# MacroStepper_v2_0.net
KiCad netlist of a schematic drawn in EAGLE
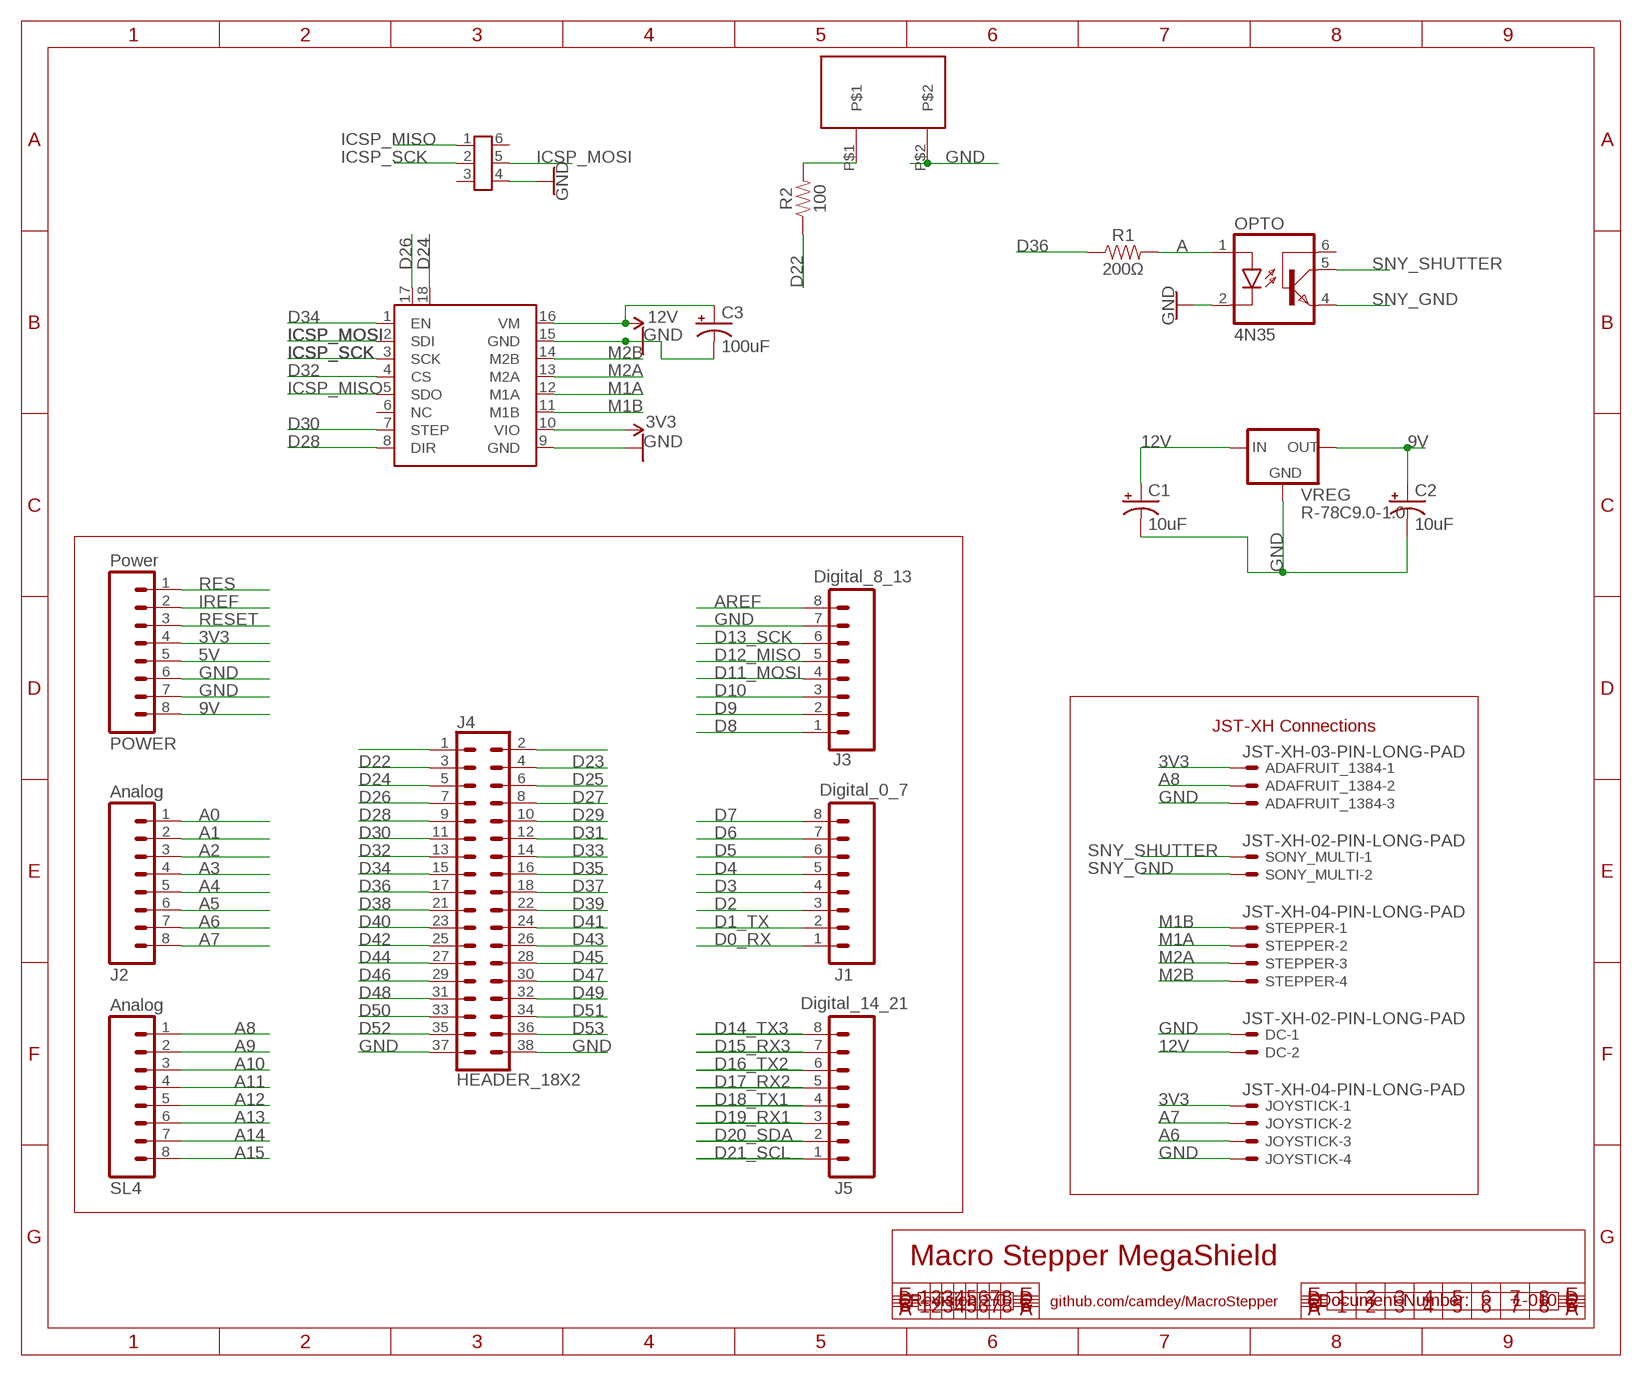
[diagram p0: schematic, sheet 1]

(export (version "E")
  (design (tool "Eeschema 10.0.6"))
  (components
    (comp (ref "ADAFRUIT_1384")
      (value "JST-XH-03-PIN-LONG-PAD")
      (footprint "eagle-import:JST-XH-03-PACKAGE-LONG-PAD")
      (libsource (lib "eagle-import") (part "JST-XH-03-PIN-LONG-PAD"))
    )
    (comp (ref "C1")
      (value "10uF")
      (footprint "eagle-import:CPOL-RADIAL-2.5MM-5MM")
      (libsource (lib "eagle-import") (part "10UF-POLAR-RADIAL-2.5MM-25V-20%"))
    )
    (comp (ref "C2")
      (value "10uF")
      (footprint "eagle-import:CPOL-RADIAL-2.5MM-5MM")
      (libsource (lib "eagle-import") (part "10UF-POLAR-RADIAL-2.5MM-25V-20%"))
    )
    (comp (ref "C3")
      (value "100uF")
      (footprint "eagle-import:CPOL-RADIAL-2.5MM-6.5MM")
      (libsource (lib "eagle-import") (part "100UF-POLAR-RADIAL-2.5MM-25V-20%"))
    )
    (comp (ref "DC")
      (value "JST-XH-02-PIN-LONG-PAD")
      (footprint "eagle-import:JST-XH-02-PACKAGE-LONG-PAD")
      (libsource (lib "eagle-import") (part "JST-XH-02-PIN-LONG-PAD"))
    )
    (comp (ref "ICSP")
      (value "MEGA_ICSP")
      (footprint "eagle-import:MEGA_ICSP")
      (libsource (lib "eagle-import") (part "MEGA_ICSP"))
    )
    (comp (ref "J1")
      (value "Digital_0_7")
      (footprint "eagle-import:1X08")
      (libsource (lib "eagle-import") (part "M08"))
    )
    (comp (ref "J2")
      (value "Analog")
      (footprint "eagle-import:1X08")
      (libsource (lib "eagle-import") (part "M08"))
    )
    (comp (ref "J3")
      (value "Digital_8_13")
      (footprint "eagle-import:1X08")
      (libsource (lib "eagle-import") (part "M08"))
    )
    (comp (ref "J4")
      (value "HEADER_18X2")
      (footprint "eagle-import:2X18")
      (libsource (lib "eagle-import") (part "HEADER_18X2"))
    )
    (comp (ref "J5")
      (value "Digital_14_21")
      (footprint "eagle-import:1X08")
      (libsource (lib "eagle-import") (part "M08"))
    )
    (comp (ref "JOYSTICK")
      (value "JST-XH-04-PIN-LONG-PAD")
      (footprint "eagle-import:JST-XH-04-PACKAGE-LONG-PAD")
      (libsource (lib "eagle-import") (part "JST-XH-04-PIN-LONG-PAD"))
    )
    (comp (ref "OPTO")
      (value "4N35")
      (footprint "eagle-import:DIL06")
      (fields (field (name "MF") "FAIRCHILD SEMICONDUCTOR"))
      (libsource (lib "eagle-import") (part "4N35"))
    )
    (comp (ref "PIEZO")
      (value "PS1240P02BT")
      (footprint "eagle-import:PS1240P02BT")
      (fields (field (name "MF") "TDK"))
      (libsource (lib "eagle-import") (part "PS1240P02BT"))
    )
    (comp (ref "POWER")
      (value "Power")
      (footprint "eagle-import:1X08")
      (libsource (lib "eagle-import") (part "M08"))
    )
    (comp (ref "R1")
      (value "200Ω")
      (footprint "eagle-import:AXIAL-0.3")
      (libsource (lib "eagle-import") (part "RESISTORAXIAL-0.3"))
    )
    (comp (ref "R2")
      (value "100")
      (footprint "eagle-import:AXIAL-0.3")
      (libsource (lib "eagle-import") (part "100OHM-HORIZ-1/4W-1%"))
    )
    (comp (ref "SL4")
      (value "Analog")
      (footprint "eagle-import:1X08")
      (libsource (lib "eagle-import") (part "M08"))
    )
    (comp (ref "SONY_MULTI")
      (value "JST-XH-02-PIN-LONG-PAD")
      (footprint "eagle-import:JST-XH-02-PACKAGE-LONG-PAD")
      (libsource (lib "eagle-import") (part "JST-XH-02-PIN-LONG-PAD"))
    )
    (comp (ref "STEPPER")
      (value "JST-XH-04-PIN-LONG-PAD")
      (footprint "eagle-import:JST-XH-04-PACKAGE-LONG-PAD")
      (libsource (lib "eagle-import") (part "JST-XH-04-PIN-LONG-PAD"))
    )
    (comp (ref "TMC2130")
      (value "TMC2130")
      (footprint "eagle-import:DIL16")
      (libsource (lib "eagle-import") (part "TMC2130"))
    )
    (comp (ref "VREG")
      (value "R-78C9.0-1.0")
      (footprint "eagle-import:SIP3")
      (fields (field (name "MF") "Recom"))
      (libsource (lib "eagle-import") (part "R-78C-1.09.0"))
    )
  )
  (nets
    (net (code "1") (name "/5V") (class "Default")
      (node (ref "POWER") (pin "5") (pinfunction "5_5") (pintype "passive"))
    )
    (net (code "2") (name "/9V") (class "Default")
      (node (ref "C2") (pin "1") (pinfunction "+_1") (pintype "passive"))
      (node (ref "POWER") (pin "8") (pinfunction "8_8") (pintype "passive"))
      (node (ref "VREG") (pin "3") (pinfunction "OUT_3") (pintype "passive"))
    )
    (net (code "3") (name "/A") (class "Default")
      (node (ref "OPTO") (pin "1") (pinfunction "A_1") (pintype "passive"))
      (node (ref "R1") (pin "P$2") (pinfunction "2_P$2") (pintype "passive"))
    )
    (net (code "4") (name "/A0") (class "Default")
      (node (ref "J2") (pin "1") (pinfunction "1_1") (pintype "passive"))
    )
    (net (code "5") (name "/A1") (class "Default")
      (node (ref "J2") (pin "2") (pinfunction "2_2") (pintype "passive"))
    )
    (net (code "6") (name "/A2") (class "Default")
      (node (ref "J2") (pin "3") (pinfunction "3_3") (pintype "passive"))
    )
    (net (code "7") (name "/A3") (class "Default")
      (node (ref "J2") (pin "4") (pinfunction "4_4") (pintype "passive"))
    )
    (net (code "8") (name "/A4") (class "Default")
      (node (ref "J2") (pin "5") (pinfunction "5_5") (pintype "passive"))
    )
    (net (code "9") (name "/A5") (class "Default")
      (node (ref "J2") (pin "6") (pinfunction "6_6") (pintype "passive"))
    )
    (net (code "10") (name "/A6") (class "Default")
      (node (ref "J2") (pin "7") (pinfunction "7_7") (pintype "passive"))
      (node (ref "JOYSTICK") (pin "3") (pinfunction "S_3") (pintype "passive"))
    )
    (net (code "11") (name "/A7") (class "Default")
      (node (ref "J2") (pin "8") (pinfunction "8_8") (pintype "passive"))
      (node (ref "JOYSTICK") (pin "2") (pinfunction "S_2") (pintype "passive"))
    )
    (net (code "12") (name "/A8") (class "Default")
      (node (ref "ADAFRUIT_1384") (pin "2") (pinfunction "S_2") (pintype "passive"))
      (node (ref "SL4") (pin "1") (pinfunction "1_1") (pintype "passive"))
    )
    (net (code "13") (name "/A9") (class "Default")
      (node (ref "SL4") (pin "2") (pinfunction "2_2") (pintype "passive"))
    )
    (net (code "14") (name "/A10") (class "Default")
      (node (ref "SL4") (pin "3") (pinfunction "3_3") (pintype "passive"))
    )
    (net (code "15") (name "/A11") (class "Default")
      (node (ref "SL4") (pin "4") (pinfunction "4_4") (pintype "passive"))
    )
    (net (code "16") (name "/A12") (class "Default")
      (node (ref "SL4") (pin "5") (pinfunction "5_5") (pintype "passive"))
    )
    (net (code "17") (name "/A13") (class "Default")
      (node (ref "SL4") (pin "6") (pinfunction "6_6") (pintype "passive"))
    )
    (net (code "18") (name "/A14") (class "Default")
      (node (ref "SL4") (pin "7") (pinfunction "7_7") (pintype "passive"))
    )
    (net (code "19") (name "/A15") (class "Default")
      (node (ref "SL4") (pin "8") (pinfunction "8_8") (pintype "passive"))
    )
    (net (code "20") (name "/AREF") (class "Default")
      (node (ref "J3") (pin "8") (pinfunction "8_8") (pintype "passive"))
    )
    (net (code "21") (name "/D0_RX") (class "Default")
      (node (ref "J1") (pin "1") (pinfunction "1_1") (pintype "passive"))
    )
    (net (code "22") (name "/D1_TX") (class "Default")
      (node (ref "J1") (pin "2") (pinfunction "2_2") (pintype "passive"))
    )
    (net (code "23") (name "/D2") (class "Default")
      (node (ref "J1") (pin "3") (pinfunction "3_3") (pintype "passive"))
    )
    (net (code "24") (name "/D3") (class "Default")
      (node (ref "J1") (pin "4") (pinfunction "4_4") (pintype "passive"))
    )
    (net (code "25") (name "/D4") (class "Default")
      (node (ref "J1") (pin "5") (pinfunction "5_5") (pintype "passive"))
    )
    (net (code "26") (name "/D5") (class "Default")
      (node (ref "J1") (pin "6") (pinfunction "6_6") (pintype "passive"))
    )
    (net (code "27") (name "/D6") (class "Default")
      (node (ref "J1") (pin "7") (pinfunction "7_7") (pintype "passive"))
    )
    (net (code "28") (name "/D7") (class "Default")
      (node (ref "J1") (pin "8") (pinfunction "8_8") (pintype "passive"))
    )
    (net (code "29") (name "/D8") (class "Default")
      (node (ref "J3") (pin "1") (pinfunction "1_1") (pintype "passive"))
    )
    (net (code "30") (name "/D9") (class "Default")
      (node (ref "J3") (pin "2") (pinfunction "2_2") (pintype "passive"))
    )
    (net (code "31") (name "/D10") (class "Default")
      (node (ref "J3") (pin "3") (pinfunction "3_3") (pintype "passive"))
    )
    (net (code "32") (name "/D11_MOSI") (class "Default")
      (node (ref "J3") (pin "4") (pinfunction "4_4") (pintype "passive"))
    )
    (net (code "33") (name "/D12_MISO") (class "Default")
      (node (ref "J3") (pin "5") (pinfunction "5_5") (pintype "passive"))
    )
    (net (code "34") (name "/D13_SCK") (class "Default")
      (node (ref "J3") (pin "6") (pinfunction "6_6") (pintype "passive"))
    )
    (net (code "35") (name "/D14_TX3") (class "Default")
      (node (ref "J5") (pin "8") (pinfunction "8_8") (pintype "passive"))
    )
    (net (code "36") (name "/D15_RX3") (class "Default")
      (node (ref "J5") (pin "7") (pinfunction "7_7") (pintype "passive"))
    )
    (net (code "37") (name "/D16_TX2") (class "Default")
      (node (ref "J5") (pin "6") (pinfunction "6_6") (pintype "passive"))
    )
    (net (code "38") (name "/D17_RX2") (class "Default")
      (node (ref "J5") (pin "5") (pinfunction "5_5") (pintype "passive"))
    )
    (net (code "39") (name "/D18_TX1") (class "Default")
      (node (ref "J5") (pin "4") (pinfunction "4_4") (pintype "passive"))
    )
    (net (code "40") (name "/D19_RX1") (class "Default")
      (node (ref "J5") (pin "3") (pinfunction "3_3") (pintype "passive"))
    )
    (net (code "41") (name "/D20_SDA") (class "Default")
      (node (ref "J5") (pin "2") (pinfunction "2_2") (pintype "passive"))
    )
    (net (code "42") (name "/D21_SCL") (class "Default")
      (node (ref "J5") (pin "1") (pinfunction "1_1") (pintype "passive"))
    )
    (net (code "43") (name "/D22") (class "Default")
      (node (ref "J4") (pin "3") (pinfunction "D22_3") (pintype "bidirectional"))
      (node (ref "R2") (pin "P$1") (pinfunction "1_P$1") (pintype "passive"))
    )
    (net (code "44") (name "/D23") (class "Default")
      (node (ref "J4") (pin "4") (pinfunction "D23_4") (pintype "bidirectional"))
    )
    (net (code "45") (name "/D24") (class "Default")
      (node (ref "J4") (pin "5") (pinfunction "D24_5") (pintype "bidirectional"))
      (node (ref "TMC2130") (pin "18") (pinfunction "DIAG1_18") (pintype "output"))
    )
    (net (code "46") (name "/D25") (class "Default")
      (node (ref "J4") (pin "6") (pinfunction "D25_6") (pintype "bidirectional"))
    )
    (net (code "47") (name "/D26") (class "Default")
      (node (ref "J4") (pin "7") (pinfunction "D26_7") (pintype "bidirectional"))
      (node (ref "TMC2130") (pin "17") (pinfunction "DIAG0_17") (pintype "output"))
    )
    (net (code "48") (name "/D27") (class "Default")
      (node (ref "J4") (pin "8") (pinfunction "D27_8") (pintype "bidirectional"))
    )
    (net (code "49") (name "/D28") (class "Default")
      (node (ref "J4") (pin "9") (pinfunction "D28_9") (pintype "bidirectional"))
      (node (ref "TMC2130") (pin "8") (pinfunction "DIR_8") (pintype "input"))
    )
    (net (code "50") (name "/D29") (class "Default")
      (node (ref "J4") (pin "10") (pinfunction "D29_10") (pintype "bidirectional"))
    )
    (net (code "51") (name "/D30") (class "Default")
      (node (ref "J4") (pin "11") (pinfunction "D30_11") (pintype "bidirectional"))
      (node (ref "TMC2130") (pin "7") (pinfunction "STEP_7") (pintype "input"))
    )
    (net (code "52") (name "/D31") (class "Default")
      (node (ref "J4") (pin "12") (pinfunction "D31_12") (pintype "bidirectional"))
    )
    (net (code "53") (name "/D32") (class "Default")
      (node (ref "J4") (pin "13") (pinfunction "D32_13") (pintype "bidirectional"))
      (node (ref "TMC2130") (pin "4") (pinfunction "CS_4") (pintype "input"))
    )
    (net (code "54") (name "/D33") (class "Default")
      (node (ref "J4") (pin "14") (pinfunction "D33_14") (pintype "bidirectional"))
    )
    (net (code "55") (name "/D34") (class "Default")
      (node (ref "J4") (pin "15") (pinfunction "D34_15") (pintype "bidirectional"))
      (node (ref "TMC2130") (pin "1") (pinfunction "EN_1") (pintype "input"))
    )
    (net (code "56") (name "/D35") (class "Default")
      (node (ref "J4") (pin "16") (pinfunction "D35_16") (pintype "bidirectional"))
    )
    (net (code "57") (name "/D36") (class "Default")
      (node (ref "J4") (pin "17") (pinfunction "D36_17") (pintype "bidirectional"))
      (node (ref "R1") (pin "P$1") (pinfunction "1_P$1") (pintype "passive"))
    )
    (net (code "58") (name "/D37") (class "Default")
      (node (ref "J4") (pin "18") (pinfunction "D37_18") (pintype "bidirectional"))
    )
    (net (code "59") (name "/D38") (class "Default")
      (node (ref "J4") (pin "21") (pinfunction "D38_21") (pintype "bidirectional"))
    )
    (net (code "60") (name "/D39") (class "Default")
      (node (ref "J4") (pin "22") (pinfunction "D39_22") (pintype "bidirectional"))
    )
    (net (code "61") (name "/D40") (class "Default")
      (node (ref "J4") (pin "23") (pinfunction "D40_23") (pintype "bidirectional"))
    )
    (net (code "62") (name "/D41") (class "Default")
      (node (ref "J4") (pin "24") (pinfunction "D41_24") (pintype "bidirectional"))
    )
    (net (code "63") (name "/D42") (class "Default")
      (node (ref "J4") (pin "25") (pinfunction "D42_25") (pintype "bidirectional"))
    )
    (net (code "64") (name "/D43") (class "Default")
      (node (ref "J4") (pin "26") (pinfunction "D43_26") (pintype "bidirectional"))
    )
    (net (code "65") (name "/D44") (class "Default")
      (node (ref "J4") (pin "27") (pinfunction "D44_27") (pintype "bidirectional"))
    )
    (net (code "66") (name "/D45") (class "Default")
      (node (ref "J4") (pin "28") (pinfunction "D45_28") (pintype "bidirectional"))
    )
    (net (code "67") (name "/D46") (class "Default")
      (node (ref "J4") (pin "29") (pinfunction "D46_29") (pintype "bidirectional"))
    )
    (net (code "68") (name "/D47") (class "Default")
      (node (ref "J4") (pin "30") (pinfunction "D47_30") (pintype "bidirectional"))
    )
    (net (code "69") (name "/D48") (class "Default")
      (node (ref "J4") (pin "31") (pinfunction "D48_31") (pintype "bidirectional"))
    )
    (net (code "70") (name "/D49") (class "Default")
      (node (ref "J4") (pin "32") (pinfunction "D49_32") (pintype "bidirectional"))
    )
    (net (code "71") (name "/D50") (class "Default")
      (node (ref "J4") (pin "33") (pinfunction "D50_33") (pintype "bidirectional"))
    )
    (net (code "72") (name "/D51") (class "Default")
      (node (ref "J4") (pin "34") (pinfunction "D51_34") (pintype "bidirectional"))
    )
    (net (code "73") (name "/D52") (class "Default")
      (node (ref "J4") (pin "35") (pinfunction "D52_35") (pintype "bidirectional"))
    )
    (net (code "74") (name "/D53") (class "Default")
      (node (ref "J4") (pin "36") (pinfunction "D53_36") (pintype "bidirectional"))
    )
    (net (code "75") (name "/ICSP_MISO") (class "Default")
      (node (ref "ICSP") (pin "1") (pinfunction "MISO_1") (pintype "bidirectional"))
      (node (ref "TMC2130") (pin "5") (pinfunction "SDO_5") (pintype "output"))
    )
    (net (code "76") (name "/ICSP_MOSI") (class "Default")
      (node (ref "ICSP") (pin "5") (pinfunction "MOSI_5") (pintype "bidirectional"))
      (node (ref "TMC2130") (pin "2") (pinfunction "SDI_2") (pintype "input"))
    )
    (net (code "77") (name "/ICSP_SCK") (class "Default")
      (node (ref "ICSP") (pin "2") (pinfunction "SCK_2") (pintype "bidirectional"))
      (node (ref "TMC2130") (pin "3") (pinfunction "SCK_3") (pintype "input"))
    )
    (net (code "78") (name "/IREF") (class "Default")
      (node (ref "POWER") (pin "2") (pinfunction "2_2") (pintype "passive"))
    )
    (net (code "79") (name "/M1A") (class "Default")
      (node (ref "STEPPER") (pin "2") (pinfunction "S_2") (pintype "passive"))
      (node (ref "TMC2130") (pin "12") (pinfunction "M1A_12") (pintype "input"))
    )
    (net (code "80") (name "/M1B") (class "Default")
      (node (ref "STEPPER") (pin "1") (pinfunction "S_1") (pintype "passive"))
      (node (ref "TMC2130") (pin "11") (pinfunction "M1B_11") (pintype "input"))
    )
    (net (code "81") (name "/M2A") (class "Default")
      (node (ref "STEPPER") (pin "3") (pinfunction "S_3") (pintype "passive"))
      (node (ref "TMC2130") (pin "13") (pinfunction "M2A_13") (pintype "input"))
    )
    (net (code "82") (name "/M2B") (class "Default")
      (node (ref "STEPPER") (pin "4") (pinfunction "S_4") (pintype "passive"))
      (node (ref "TMC2130") (pin "14") (pinfunction "M2B_14") (pintype "input"))
    )
    (net (code "83") (name "/RES") (class "Default")
      (node (ref "POWER") (pin "1") (pinfunction "1_1") (pintype "passive"))
    )
    (net (code "84") (name "/RESET") (class "Default")
      (node (ref "POWER") (pin "3") (pinfunction "3_3") (pintype "passive"))
    )
    (net (code "85") (name "/SNY_GND") (class "Default")
      (node (ref "OPTO") (pin "4") (pinfunction "EMI_4") (pintype "passive"))
      (node (ref "SONY_MULTI") (pin "2") (pinfunction "S_2") (pintype "passive"))
    )
    (net (code "86") (name "/SNY_SHUTTER") (class "Default")
      (node (ref "OPTO") (pin "5") (pinfunction "COL_5") (pintype "passive"))
      (node (ref "SONY_MULTI") (pin "1") (pinfunction "S_1") (pintype "passive"))
    )
    (net (code "87") (name "3V3") (class "Default")
      (node (ref "ADAFRUIT_1384") (pin "1") (pinfunction "S_1") (pintype "passive"))
      (node (ref "JOYSTICK") (pin "1") (pinfunction "S_1") (pintype "passive"))
      (node (ref "POWER") (pin "4") (pinfunction "4_4") (pintype "passive"))
      (node (ref "TMC2130") (pin "10") (pinfunction "VIO_10") (pintype "power_in"))
    )
    (net (code "88") (name "12V") (class "Default")
      (node (ref "C1") (pin "1") (pinfunction "+_1") (pintype "passive"))
      (node (ref "C3") (pin "1") (pinfunction "+_1") (pintype "passive"))
      (node (ref "DC") (pin "2") (pinfunction "S_2") (pintype "passive"))
      (node (ref "TMC2130") (pin "16") (pinfunction "VM_16") (pintype "power_in"))
      (node (ref "VREG") (pin "1") (pinfunction "IN_1") (pintype "input"))
    )
    (net (code "89") (name "GND") (class "Default")
      (node (ref "ADAFRUIT_1384") (pin "3") (pinfunction "S_3") (pintype "passive"))
      (node (ref "C1") (pin "2") (pinfunction "-_2") (pintype "passive"))
      (node (ref "C2") (pin "2") (pinfunction "-_2") (pintype "passive"))
      (node (ref "C3") (pin "2") (pinfunction "-_2") (pintype "passive"))
      (node (ref "DC") (pin "1") (pinfunction "S_1") (pintype "passive"))
      (node (ref "ICSP") (pin "4") (pinfunction "GND_4") (pintype "power_in"))
      (node (ref "J3") (pin "7") (pinfunction "7_7") (pintype "passive"))
      (node (ref "J4") (pin "37") (pinfunction "GND_37") (pintype "power_in"))
      (node (ref "J4") (pin "38") (pinfunction "GND_38") (pintype "power_in"))
      (node (ref "JOYSTICK") (pin "4") (pinfunction "S_4") (pintype "passive"))
      (node (ref "OPTO") (pin "2") (pinfunction "C_2") (pintype "passive"))
      (node (ref "PIEZO") (pin "P$2") (pinfunction "P$2_P$2") (pintype "bidirectional"))
      (node (ref "POWER") (pin "6") (pinfunction "6_6") (pintype "passive"))
      (node (ref "POWER") (pin "7") (pinfunction "7_7") (pintype "passive"))
      (node (ref "TMC2130") (pin "15") (pinfunction "GND_15") (pintype "power_in"))
      (node (ref "TMC2130") (pin "9") (pinfunction "GND_9") (pintype "power_in"))
      (node (ref "VREG") (pin "2") (pinfunction "GND_2") (pintype "input"))
    )
    (net (code "90") (name "Net-(R2-2)") (class "Default")
      (node (ref "PIEZO") (pin "P$1") (pinfunction "P$1_P$1") (pintype "bidirectional"))
      (node (ref "R2") (pin "P$2") (pinfunction "2_P$2") (pintype "passive"))
    )
    (net (code "91") (name "unconnected-(ICSP-5V-Pad6)") (class "Default")
      (node (ref "ICSP") (pin "6") (pinfunction "5V_6") (pintype "no_connect"))
    )
    (net (code "92") (name "unconnected-(ICSP-RST-Pad3)") (class "Default")
      (node (ref "ICSP") (pin "3") (pinfunction "RST_3") (pintype "no_connect"))
    )
    (net (code "93") (name "unconnected-(J4-5V-Pad1)") (class "Default")
      (node (ref "J4") (pin "1") (pinfunction "5V_1") (pintype "power_in"))
    )
    (net (code "94") (name "unconnected-(J4-5V-Pad2)") (class "Default")
      (node (ref "J4") (pin "2") (pinfunction "5V_2") (pintype "power_in"))
    )
    (net (code "95") (name "unconnected-(OPTO-BAS-Pad6)") (class "Default")
      (node (ref "OPTO") (pin "6") (pinfunction "BAS_6") (pintype "passive"))
    )
    (net (code "96") (name "unconnected-(TMC2130-NC-Pad6)") (class "Default")
      (node (ref "TMC2130") (pin "6") (pinfunction "NC_6") (pintype "no_connect"))
    )
  )
)
